# Grove_Breakout_Board.net
KiCad netlist of a schematic drawn in Altium Designer
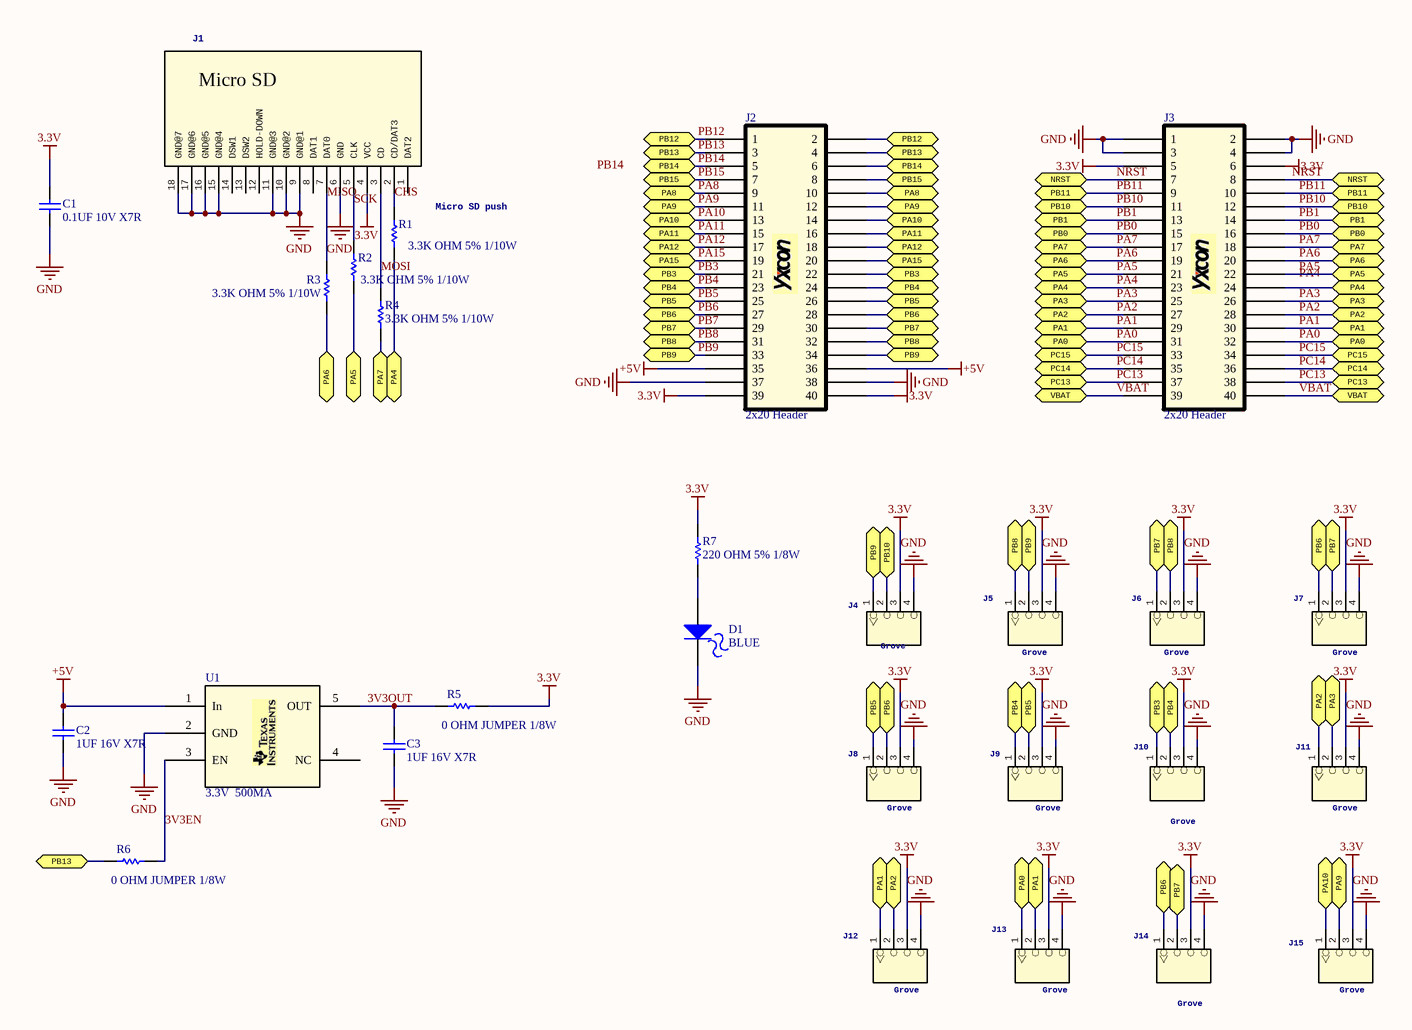
[diagram p0: Grove Breakout Board.SchDoc]

(export (version "E")
  (design (tool "Eeschema 10.0.6"))
  (components
    (comp (ref "C1")
      (value "0.1UF 10V X7R")
      (footprint "SMD-0603C")
      (description "CAP CER 0.1UF 10V X7R 0603")
      (fields (field (name "MANUFACTURER") "Wurth Electronics Inc."))
      (libsource (lib "CircuitStudioSchematic.Lib") (part "885012206020"))
    )
    (comp (ref "C2")
      (value "1UF 16V X7R")
      (footprint "SMD-0603C")
      (description "CAP CER 1UF 16V X7R 0603")
      (fields (field (name "MANUFACTURER") "Samsung Electro-Mechanics"))
      (libsource (lib "CircuitStudioSchematic.Lib") (part "CL10B105MO8NNWC"))
    )
    (comp (ref "C3")
      (value "1UF 16V X7R")
      (footprint "SMD-0603C")
      (description "CAP CER 1UF 16V X7R 0603")
      (fields (field (name "MANUFACTURER") "Samsung Electro-Mechanics"))
      (libsource (lib "CircuitStudioSchematic.Lib") (part "CL10B105MO8NNWC"))
    )
    (comp (ref "D1")
      (value "BLUE")
      (footprint "0603 LED BLUE")
      (description "LED BLUE CLEAR CHIP SMD")
      (fields (field (name "MANUFACTURER") "Lite-On Inc."))
      (libsource (lib "CircuitStudioSchematic.Lib") (part "LTST-C190TBKT"))
    )
    (comp (ref "J1")
      (value "Micro SD push")
      (footprint "JAE_ST11H_MicroSD")
      (description "CONN MICRO SD CARD PUSH-PUSH R/A")
      (fields (field (name "MANUFACTURER") "JAE Electronics"))
      (libsource (lib "CircuitStudioSchematic.Lib") (part "ST11S008V4HR2000"))
    )
    (comp (ref "J2")
      (value "2x20 Header")
      (footprint "2.54mm 2x20 8.5mm 5 mm")
      (description "2x20 Header 2.54 mm 5 mm x 8.5 mm")
      (fields (field (name "MANUFACTURER") "Xycon"))
      (libsource (lib "CircuitStudioSchematic.Lib") (part "F185-1220A0BSYA1"))
    )
    (comp (ref "J3")
      (value "2x20 Header")
      (footprint "2.54mm 2x20 8.5mm 5 mm")
      (description "2x20 Header 2.54 mm 5 mm x 8.5 mm")
      (fields (field (name "MANUFACTURER") "Xycon"))
      (libsource (lib "CircuitStudioSchematic.Lib") (part "F185-1220A0BSYA1"))
    )
    (comp (ref "J4")
      (value "Grove")
      (footprint "HW4-2.0 - Straight")
      (description "GROVE 2MM 4PIN CONN 10PACK")
      (fields (field (name "MANUFACTURER") "Seeed Technology Co., Ltd"))
      (libsource (lib "CircuitStudioSchematic.Lib") (part "320110033"))
    )
    (comp (ref "J5")
      (value "Grove")
      (footprint "HW4-2.0 - Straight")
      (description "GROVE 2MM 4PIN CONN 10PACK")
      (fields (field (name "MANUFACTURER") "Seeed Technology Co., Ltd"))
      (libsource (lib "CircuitStudioSchematic.Lib") (part "320110033"))
    )
    (comp (ref "J6")
      (value "Grove")
      (footprint "HW4-2.0 - Straight")
      (description "GROVE 2MM 4PIN CONN 10PACK")
      (fields (field (name "MANUFACTURER") "Seeed Technology Co., Ltd"))
      (libsource (lib "CircuitStudioSchematic.Lib") (part "320110033"))
    )
    (comp (ref "J7")
      (value "Grove")
      (footprint "HW4-2.0 - Straight")
      (description "GROVE 2MM 4PIN CONN 10PACK")
      (fields (field (name "MANUFACTURER") "Seeed Technology Co., Ltd"))
      (libsource (lib "CircuitStudioSchematic.Lib") (part "320110033"))
    )
    (comp (ref "J8")
      (value "Grove")
      (footprint "HW4-2.0 - Straight")
      (description "GROVE 2MM 4PIN CONN 10PACK")
      (fields (field (name "MANUFACTURER") "Seeed Technology Co., Ltd"))
      (libsource (lib "CircuitStudioSchematic.Lib") (part "320110033"))
    )
    (comp (ref "J9")
      (value "Grove")
      (footprint "HW4-2.0 - Straight")
      (description "GROVE 2MM 4PIN CONN 10PACK")
      (fields (field (name "MANUFACTURER") "Seeed Technology Co., Ltd"))
      (libsource (lib "CircuitStudioSchematic.Lib") (part "320110033"))
    )
    (comp (ref "J10")
      (value "Grove")
      (footprint "HW4-2.0 - Straight")
      (description "GROVE 2MM 4PIN CONN 10PACK")
      (fields (field (name "MANUFACTURER") "Seeed Technology Co., Ltd"))
      (libsource (lib "CircuitStudioSchematic.Lib") (part "320110033"))
    )
    (comp (ref "J11")
      (value "Grove")
      (footprint "HW4-2.0 - Straight")
      (description "GROVE 2MM 4PIN CONN 10PACK")
      (fields (field (name "MANUFACTURER") "Seeed Technology Co., Ltd"))
      (libsource (lib "CircuitStudioSchematic.Lib") (part "320110033"))
    )
    (comp (ref "J12")
      (value "Grove")
      (footprint "HW4-2.0 - Straight")
      (description "GROVE 2MM 4PIN CONN 10PACK")
      (fields (field (name "MANUFACTURER") "Seeed Technology Co., Ltd"))
      (libsource (lib "CircuitStudioSchematic.Lib") (part "320110033"))
    )
    (comp (ref "J13")
      (value "Grove")
      (footprint "HW4-2.0 - Straight")
      (description "GROVE 2MM 4PIN CONN 10PACK")
      (fields (field (name "MANUFACTURER") "Seeed Technology Co., Ltd"))
      (libsource (lib "CircuitStudioSchematic.Lib") (part "320110033"))
    )
    (comp (ref "J14")
      (value "Grove")
      (footprint "HW4-2.0 - Straight")
      (description "GROVE 2MM 4PIN CONN 10PACK")
      (fields (field (name "MANUFACTURER") "Seeed Technology Co., Ltd"))
      (libsource (lib "CircuitStudioSchematic.Lib") (part "320110033"))
    )
    (comp (ref "J15")
      (value "Grove")
      (footprint "HW4-2.0 - Straight")
      (description "GROVE 2MM 4PIN CONN 10PACK")
      (fields (field (name "MANUFACTURER") "Seeed Technology Co., Ltd"))
      (libsource (lib "CircuitStudioSchematic.Lib") (part "320110033"))
    )
    (comp (ref "R1")
      (value "3.3K OHM 5% 1/10W")
      (footprint "SMD-0603-RES")
      (description "RES SMD 3.3K OHM 5% 1/10W 0603")
      (fields (field (name "MANUFACTURER") "Yageo"))
      (libsource (lib "CircuitStudioSchematic.Lib") (part "RC0603JR-073K3L"))
    )
    (comp (ref "R2")
      (value "3.3K OHM 5% 1/10W")
      (footprint "SMD-0603-RES")
      (description "RES SMD 3.3K OHM 5% 1/10W 0603")
      (fields (field (name "MANUFACTURER") "Yageo"))
      (libsource (lib "CircuitStudioSchematic.Lib") (part "RC0603JR-073K3L"))
    )
    (comp (ref "R3")
      (value "3.3K OHM 5% 1/10W")
      (footprint "SMD-0603-RES")
      (description "RES SMD 3.3K OHM 5% 1/10W 0603")
      (fields (field (name "MANUFACTURER") "Yageo"))
      (libsource (lib "CircuitStudioSchematic.Lib") (part "RC0603JR-073K3L"))
    )
    (comp (ref "R4")
      (value "3.3K OHM 5% 1/10W")
      (footprint "SMD-0603-RES")
      (description "RES SMD 3.3K OHM 5% 1/10W 0603")
      (fields (field (name "MANUFACTURER") "Yageo"))
      (libsource (lib "CircuitStudioSchematic.Lib") (part "RC0603JR-073K3L"))
    )
    (comp (ref "R5")
      (value "0 OHM JUMPER 1/8W")
      (footprint "SMD-0805-RES")
      (description "RES SMD 0 OHM JUMPER 1/8W 0805")
      (fields (field (name "MANUFACTURER") "Yageo"))
      (libsource (lib "CircuitStudioSchematic.Lib") (part "RC0805JR-070RL"))
    )
    (comp (ref "R6")
      (value "0 OHM JUMPER 1/8W")
      (footprint "SMD-0805-RES")
      (description "RES SMD 0 OHM JUMPER 1/8W 0805")
      (fields (field (name "MANUFACTURER") "Yageo"))
      (libsource (lib "CircuitStudioSchematic.Lib") (part "RC0805JR-070RL"))
    )
    (comp (ref "R7")
      (value "220 OHM 5% 1/8W")
      (footprint "SMD-0805-RES")
      (description "RES SMD 220 OHM 5% 1/8W 0805")
      (fields (field (name "MANUFACTURER") "Yageo"))
      (libsource (lib "CircuitStudioSchematic.Lib") (part "RC0805JR-07220RL"))
    )
    (comp (ref "U1")
      (value "3.3V  500MA")
      (footprint "SOT-23-5 TI")
      (description "IC REG LINEAR 3.3V 500MA SOT23-5")
      (fields (field (name "MANUFACTURER") "Texas Instruments"))
      (libsource (lib "CircuitStudioSchematic.Lib") (part "TLV75533PDBVR"))
    )
  )
  (nets
    (net (code "1") (name "+5V") (class "Default")
      (node (ref "C2") (pin "2") (pinfunction "2_2") (pintype "passive"))
      (node (ref "J2") (pin "35") (pinfunction "35_35") (pintype "passive"))
      (node (ref "J2") (pin "36") (pinfunction "36_36") (pintype "passive"))
      (node (ref "U1") (pin "1") (pinfunction "In_1") (pintype "passive"))
    )
    (net (code "2") (name "/3V3EN") (class "Default")
      (node (ref "R6") (pin "2") (pinfunction "2_2") (pintype "passive"))
      (node (ref "U1") (pin "3") (pinfunction "EN_3") (pintype "passive"))
    )
    (net (code "3") (name "/3V3OUT") (class "Default")
      (node (ref "C3") (pin "2") (pinfunction "2_2") (pintype "passive"))
      (node (ref "R5") (pin "1") (pinfunction "1_1") (pintype "passive"))
      (node (ref "U1") (pin "5") (pinfunction "OUT_5") (pintype "passive"))
    )
    (net (code "4") (name "/CHS") (class "Default")
      (node (ref "J1") (pin "2") (pinfunction "CD/DAT3_2") (pintype "passive"))
      (node (ref "R1") (pin "2") (pinfunction "2_2") (pintype "passive"))
    )
    (net (code "5") (name "/MISO") (class "Default")
      (node (ref "J1") (pin "7") (pinfunction "DAT0_7") (pintype "passive"))
      (node (ref "R3") (pin "2") (pinfunction "2_2") (pintype "passive"))
    )
    (net (code "6") (name "/MOSI") (class "Default")
      (node (ref "J1") (pin "3") (pinfunction "CD_3") (pintype "passive"))
      (node (ref "R4") (pin "1") (pinfunction "1_1") (pintype "passive"))
    )
    (net (code "7") (name "/NRST") (class "Default")
      (node (ref "J3") (pin "7") (pinfunction "7_7") (pintype "passive"))
      (node (ref "J3") (pin "8") (pinfunction "8_8") (pintype "passive"))
    )
    (net (code "8") (name "/PA0") (class "Default")
      (node (ref "J13") (pin "1") (pinfunction "1_1") (pintype "passive"))
      (node (ref "J3") (pin "31") (pinfunction "31_31") (pintype "passive"))
      (node (ref "J3") (pin "32") (pinfunction "32_32") (pintype "passive"))
    )
    (net (code "9") (name "/PA1") (class "Default")
      (node (ref "J12") (pin "1") (pinfunction "1_1") (pintype "passive"))
      (node (ref "J13") (pin "2") (pinfunction "2_2") (pintype "passive"))
      (node (ref "J3") (pin "29") (pinfunction "29_29") (pintype "passive"))
      (node (ref "J3") (pin "30") (pinfunction "30_30") (pintype "passive"))
    )
    (net (code "10") (name "/PA2") (class "Default")
      (node (ref "J11") (pin "1") (pinfunction "1_1") (pintype "passive"))
      (node (ref "J12") (pin "2") (pinfunction "2_2") (pintype "passive"))
      (node (ref "J3") (pin "27") (pinfunction "27_27") (pintype "passive"))
      (node (ref "J3") (pin "28") (pinfunction "28_28") (pintype "passive"))
    )
    (net (code "11") (name "/PA3") (class "Default")
      (node (ref "J11") (pin "2") (pinfunction "2_2") (pintype "passive"))
      (node (ref "J3") (pin "25") (pinfunction "25_25") (pintype "passive"))
      (node (ref "J3") (pin "26") (pinfunction "26_26") (pintype "passive"))
    )
    (net (code "12") (name "/PA4") (class "Default")
      (node (ref "J3") (pin "23") (pinfunction "23_23") (pintype "passive"))
      (node (ref "J3") (pin "24") (pinfunction "24_24") (pintype "passive"))
      (node (ref "R1") (pin "1") (pinfunction "1_1") (pintype "passive"))
    )
    (net (code "13") (name "/PA5") (class "Default")
      (node (ref "J3") (pin "21") (pinfunction "21_21") (pintype "passive"))
      (node (ref "J3") (pin "22") (pinfunction "22_22") (pintype "passive"))
      (node (ref "R2") (pin "1") (pinfunction "1_1") (pintype "passive"))
    )
    (net (code "14") (name "/PA6") (class "Default")
      (node (ref "J3") (pin "19") (pinfunction "19_19") (pintype "passive"))
      (node (ref "J3") (pin "20") (pinfunction "20_20") (pintype "passive"))
      (node (ref "R3") (pin "1") (pinfunction "1_1") (pintype "passive"))
    )
    (net (code "15") (name "/PA7") (class "Default")
      (node (ref "J3") (pin "17") (pinfunction "17_17") (pintype "passive"))
      (node (ref "J3") (pin "18") (pinfunction "18_18") (pintype "passive"))
      (node (ref "R4") (pin "2") (pinfunction "2_2") (pintype "passive"))
    )
    (net (code "16") (name "/PA8") (class "Default")
      (node (ref "J2") (pin "10") (pinfunction "10_10") (pintype "passive"))
      (node (ref "J2") (pin "9") (pinfunction "9_9") (pintype "passive"))
    )
    (net (code "17") (name "/PA9") (class "Default")
      (node (ref "J15") (pin "2") (pinfunction "2_2") (pintype "passive"))
      (node (ref "J2") (pin "11") (pinfunction "11_11") (pintype "passive"))
      (node (ref "J2") (pin "12") (pinfunction "12_12") (pintype "passive"))
    )
    (net (code "18") (name "/PA10") (class "Default")
      (node (ref "J15") (pin "1") (pinfunction "1_1") (pintype "passive"))
      (node (ref "J2") (pin "13") (pinfunction "13_13") (pintype "passive"))
      (node (ref "J2") (pin "14") (pinfunction "14_14") (pintype "passive"))
    )
    (net (code "19") (name "/PA11") (class "Default")
      (node (ref "J2") (pin "15") (pinfunction "15_15") (pintype "passive"))
      (node (ref "J2") (pin "16") (pinfunction "16_16") (pintype "passive"))
    )
    (net (code "20") (name "/PA12") (class "Default")
      (node (ref "J2") (pin "17") (pinfunction "17_17") (pintype "passive"))
      (node (ref "J2") (pin "18") (pinfunction "18_18") (pintype "passive"))
    )
    (net (code "21") (name "/PA15") (class "Default")
      (node (ref "J2") (pin "19") (pinfunction "19_19") (pintype "passive"))
      (node (ref "J2") (pin "20") (pinfunction "20_20") (pintype "passive"))
    )
    (net (code "22") (name "/PB0") (class "Default")
      (node (ref "J3") (pin "15") (pinfunction "15_15") (pintype "passive"))
      (node (ref "J3") (pin "16") (pinfunction "16_16") (pintype "passive"))
    )
    (net (code "23") (name "/PB1") (class "Default")
      (node (ref "J3") (pin "13") (pinfunction "13_13") (pintype "passive"))
      (node (ref "J3") (pin "14") (pinfunction "14_14") (pintype "passive"))
    )
    (net (code "24") (name "/PB3") (class "Default")
      (node (ref "J10") (pin "1") (pinfunction "1_1") (pintype "passive"))
      (node (ref "J2") (pin "21") (pinfunction "21_21") (pintype "passive"))
      (node (ref "J2") (pin "22") (pinfunction "22_22") (pintype "passive"))
    )
    (net (code "25") (name "/PB4") (class "Default")
      (node (ref "J10") (pin "2") (pinfunction "2_2") (pintype "passive"))
      (node (ref "J2") (pin "23") (pinfunction "23_23") (pintype "passive"))
      (node (ref "J2") (pin "24") (pinfunction "24_24") (pintype "passive"))
      (node (ref "J9") (pin "1") (pinfunction "1_1") (pintype "passive"))
    )
    (net (code "26") (name "/PB5") (class "Default")
      (node (ref "J2") (pin "25") (pinfunction "25_25") (pintype "passive"))
      (node (ref "J2") (pin "26") (pinfunction "26_26") (pintype "passive"))
      (node (ref "J8") (pin "1") (pinfunction "1_1") (pintype "passive"))
      (node (ref "J9") (pin "2") (pinfunction "2_2") (pintype "passive"))
    )
    (net (code "27") (name "/PB6") (class "Default")
      (node (ref "J14") (pin "1") (pinfunction "1_1") (pintype "passive"))
      (node (ref "J2") (pin "27") (pinfunction "27_27") (pintype "passive"))
      (node (ref "J2") (pin "28") (pinfunction "28_28") (pintype "passive"))
      (node (ref "J7") (pin "1") (pinfunction "1_1") (pintype "passive"))
      (node (ref "J8") (pin "2") (pinfunction "2_2") (pintype "passive"))
    )
    (net (code "28") (name "/PB7") (class "Default")
      (node (ref "J14") (pin "2") (pinfunction "2_2") (pintype "passive"))
      (node (ref "J2") (pin "29") (pinfunction "29_29") (pintype "passive"))
      (node (ref "J2") (pin "30") (pinfunction "30_30") (pintype "passive"))
      (node (ref "J6") (pin "1") (pinfunction "1_1") (pintype "passive"))
      (node (ref "J7") (pin "2") (pinfunction "2_2") (pintype "passive"))
    )
    (net (code "29") (name "/PB8") (class "Default")
      (node (ref "J2") (pin "31") (pinfunction "31_31") (pintype "passive"))
      (node (ref "J2") (pin "32") (pinfunction "32_32") (pintype "passive"))
      (node (ref "J5") (pin "1") (pinfunction "1_1") (pintype "passive"))
      (node (ref "J6") (pin "2") (pinfunction "2_2") (pintype "passive"))
    )
    (net (code "30") (name "/PB9") (class "Default")
      (node (ref "J2") (pin "33") (pinfunction "33_33") (pintype "passive"))
      (node (ref "J2") (pin "34") (pinfunction "34_34") (pintype "passive"))
      (node (ref "J4") (pin "1") (pinfunction "1_1") (pintype "passive"))
      (node (ref "J5") (pin "2") (pinfunction "2_2") (pintype "passive"))
    )
    (net (code "31") (name "/PB10") (class "Default")
      (node (ref "J3") (pin "11") (pinfunction "11_11") (pintype "passive"))
      (node (ref "J3") (pin "12") (pinfunction "12_12") (pintype "passive"))
      (node (ref "J4") (pin "2") (pinfunction "2_2") (pintype "passive"))
    )
    (net (code "32") (name "/PB11") (class "Default")
      (node (ref "J3") (pin "10") (pinfunction "10_10") (pintype "passive"))
      (node (ref "J3") (pin "9") (pinfunction "9_9") (pintype "passive"))
    )
    (net (code "33") (name "/PB12") (class "Default")
      (node (ref "J2") (pin "1") (pinfunction "1_1") (pintype "passive"))
      (node (ref "J2") (pin "2") (pinfunction "2_2") (pintype "passive"))
    )
    (net (code "34") (name "/PB13") (class "Default")
      (node (ref "J2") (pin "3") (pinfunction "3_3") (pintype "passive"))
      (node (ref "J2") (pin "4") (pinfunction "4_4") (pintype "passive"))
      (node (ref "R6") (pin "1") (pinfunction "1_1") (pintype "passive"))
    )
    (net (code "35") (name "/PB14") (class "Default")
      (node (ref "J2") (pin "5") (pinfunction "5_5") (pintype "passive"))
      (node (ref "J2") (pin "6") (pinfunction "6_6") (pintype "passive"))
    )
    (net (code "36") (name "/PB15") (class "Default")
      (node (ref "J2") (pin "7") (pinfunction "7_7") (pintype "passive"))
      (node (ref "J2") (pin "8") (pinfunction "8_8") (pintype "passive"))
    )
    (net (code "37") (name "/PC13") (class "Default")
      (node (ref "J3") (pin "37") (pinfunction "37_37") (pintype "passive"))
      (node (ref "J3") (pin "38") (pinfunction "38_38") (pintype "passive"))
    )
    (net (code "38") (name "/PC14") (class "Default")
      (node (ref "J3") (pin "35") (pinfunction "35_35") (pintype "passive"))
      (node (ref "J3") (pin "36") (pinfunction "36_36") (pintype "passive"))
    )
    (net (code "39") (name "/PC15") (class "Default")
      (node (ref "J3") (pin "33") (pinfunction "33_33") (pintype "passive"))
      (node (ref "J3") (pin "34") (pinfunction "34_34") (pintype "passive"))
    )
    (net (code "40") (name "/SCK") (class "Default")
      (node (ref "J1") (pin "5") (pinfunction "CLK_5") (pintype "passive"))
      (node (ref "R2") (pin "2") (pinfunction "2_2") (pintype "passive"))
    )
    (net (code "41") (name "/VBAT") (class "Default")
      (node (ref "J3") (pin "39") (pinfunction "39_39") (pintype "passive"))
      (node (ref "J3") (pin "40") (pinfunction "40_40") (pintype "passive"))
    )
    (net (code "42") (name "3.3V") (class "Default")
      (node (ref "C1") (pin "1") (pinfunction "1_1") (pintype "passive"))
      (node (ref "J1") (pin "4") (pinfunction "VCC_4") (pintype "passive"))
      (node (ref "J10") (pin "3") (pinfunction "3_3") (pintype "passive"))
      (node (ref "J11") (pin "3") (pinfunction "3_3") (pintype "passive"))
      (node (ref "J12") (pin "3") (pinfunction "3_3") (pintype "passive"))
      (node (ref "J13") (pin "3") (pinfunction "3_3") (pintype "passive"))
      (node (ref "J14") (pin "3") (pinfunction "3_3") (pintype "passive"))
      (node (ref "J15") (pin "3") (pinfunction "3_3") (pintype "passive"))
      (node (ref "J2") (pin "39") (pinfunction "39_39") (pintype "passive"))
      (node (ref "J2") (pin "40") (pinfunction "40_40") (pintype "passive"))
      (node (ref "J3") (pin "5") (pinfunction "5_5") (pintype "passive"))
      (node (ref "J3") (pin "6") (pinfunction "6_6") (pintype "passive"))
      (node (ref "J4") (pin "3") (pinfunction "3_3") (pintype "passive"))
      (node (ref "J5") (pin "3") (pinfunction "3_3") (pintype "passive"))
      (node (ref "J6") (pin "3") (pinfunction "3_3") (pintype "passive"))
      (node (ref "J7") (pin "3") (pinfunction "3_3") (pintype "passive"))
      (node (ref "J8") (pin "3") (pinfunction "3_3") (pintype "passive"))
      (node (ref "J9") (pin "3") (pinfunction "3_3") (pintype "passive"))
      (node (ref "R5") (pin "2") (pinfunction "2_2") (pintype "passive"))
      (node (ref "R7") (pin "2") (pinfunction "2_2") (pintype "passive"))
    )
    (net (code "43") (name "GND") (class "Default")
      (node (ref "C1") (pin "2") (pinfunction "2_2") (pintype "passive"))
      (node (ref "C2") (pin "1") (pinfunction "1_1") (pintype "passive"))
      (node (ref "C3") (pin "1") (pinfunction "1_1") (pintype "passive"))
      (node (ref "D1") (pin "2") (pinfunction "Cathode_2") (pintype "passive"))
      (node (ref "J1") (pin "10") (pinfunction "GND@2_10") (pintype "passive"))
      (node (ref "J1") (pin "11") (pinfunction "GND@3_11") (pintype "passive"))
      (node (ref "J1") (pin "15") (pinfunction "GND@4_15") (pintype "passive"))
      (node (ref "J1") (pin "16") (pinfunction "GND@5_16") (pintype "passive"))
      (node (ref "J1") (pin "17") (pinfunction "GND@6_17") (pintype "passive"))
      (node (ref "J1") (pin "18") (pinfunction "GND@7_18") (pintype "passive"))
      (node (ref "J1") (pin "6") (pinfunction "GND_6") (pintype "passive"))
      (node (ref "J1") (pin "9") (pinfunction "GND@1_9") (pintype "passive"))
      (node (ref "J10") (pin "4") (pinfunction "4_4") (pintype "passive"))
      (node (ref "J11") (pin "4") (pinfunction "4_4") (pintype "passive"))
      (node (ref "J12") (pin "4") (pinfunction "4_4") (pintype "passive"))
      (node (ref "J13") (pin "4") (pinfunction "4_4") (pintype "passive"))
      (node (ref "J14") (pin "4") (pinfunction "4_4") (pintype "passive"))
      (node (ref "J15") (pin "4") (pinfunction "4_4") (pintype "passive"))
      (node (ref "J2") (pin "37") (pinfunction "37_37") (pintype "passive"))
      (node (ref "J2") (pin "38") (pinfunction "38_38") (pintype "passive"))
      (node (ref "J3") (pin "1") (pinfunction "1_1") (pintype "passive"))
      (node (ref "J3") (pin "2") (pinfunction "2_2") (pintype "passive"))
      (node (ref "J3") (pin "3") (pinfunction "3_3") (pintype "passive"))
      (node (ref "J3") (pin "4") (pinfunction "4_4") (pintype "passive"))
      (node (ref "J4") (pin "4") (pinfunction "4_4") (pintype "passive"))
      (node (ref "J5") (pin "4") (pinfunction "4_4") (pintype "passive"))
      (node (ref "J6") (pin "4") (pinfunction "4_4") (pintype "passive"))
      (node (ref "J7") (pin "4") (pinfunction "4_4") (pintype "passive"))
      (node (ref "J8") (pin "4") (pinfunction "4_4") (pintype "passive"))
      (node (ref "J9") (pin "4") (pinfunction "4_4") (pintype "passive"))
      (node (ref "U1") (pin "2") (pinfunction "GND_2") (pintype "passive"))
    )
    (net (code "44") (name "Net-(D1-Anode)") (class "Default")
      (node (ref "D1") (pin "1") (pinfunction "Anode_1") (pintype "passive"))
      (node (ref "R7") (pin "1") (pinfunction "1_1") (pintype "passive"))
    )
    (net (code "45") (name "unconnected-(J1-DAT1-Pad8)") (class "Default")
      (node (ref "J1") (pin "8") (pinfunction "DAT1_8") (pintype "passive"))
    )
    (net (code "46") (name "unconnected-(J1-DAT2-Pad1)") (class "Default")
      (node (ref "J1") (pin "1") (pinfunction "DAT2_1") (pintype "passive"))
    )
    (net (code "47") (name "unconnected-(J1-DSW1-Pad14)") (class "Default")
      (node (ref "J1") (pin "14") (pinfunction "DSW1_14") (pintype "passive"))
    )
    (net (code "48") (name "unconnected-(J1-DSW2-Pad13)") (class "Default")
      (node (ref "J1") (pin "13") (pinfunction "DSW2_13") (pintype "passive"))
    )
    (net (code "49") (name "unconnected-(J1-HOLD-DOWN-Pad12)") (class "Default")
      (node (ref "J1") (pin "12") (pinfunction "HOLD-DOWN_12") (pintype "passive"))
    )
    (net (code "50") (name "unconnected-(U1-NC-Pad4)") (class "Default")
      (node (ref "U1") (pin "4") (pinfunction "NC_4") (pintype "passive"))
    )
  )
)
